# IO.net
KiCad netlist of a schematic drawn in Altium Designer
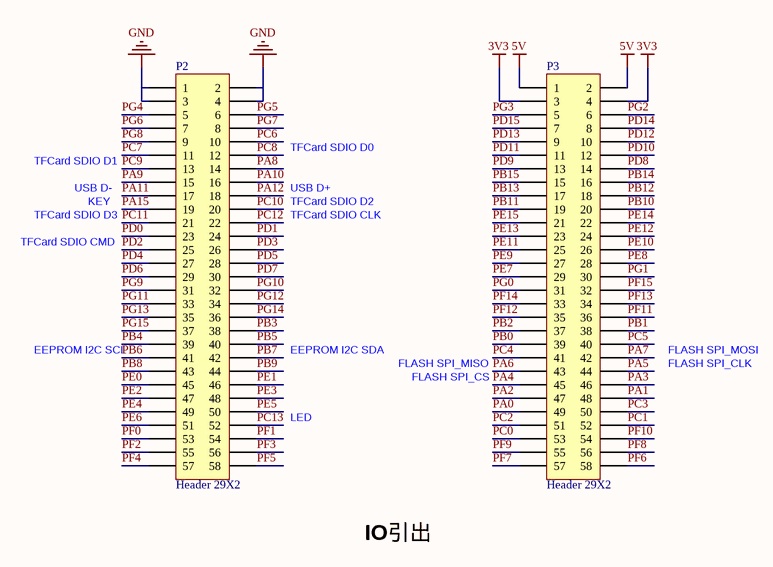
[diagram p0: 主控系统板IO引出.SchDoc]

(export (version "E")
  (design (tool "Eeschema 10.0.6"))
  (components
    (comp (ref "P2")
      (value "Header 29X2")
      (footprint "HDR2X29")
      (libsource (lib "altium-import") (part "root_0_Header 29X2_"))
    )
    (comp (ref "P3")
      (value "Header 29X2")
      (footprint "HDR2X29")
      (libsource (lib "altium-import") (part "root_0_Header 29X2_"))
    )
  )
  (nets
    (net (code "1") (name "/PA0") (class "Default")
      (node (ref "P3") (pin "49") (pinfunction "49_49") (pintype "passive"))
    )
    (net (code "2") (name "/PA1") (class "Default")
      (node (ref "P3") (pin "48") (pinfunction "48_48") (pintype "passive"))
    )
    (net (code "3") (name "/PA2") (class "Default")
      (node (ref "P3") (pin "47") (pinfunction "47_47") (pintype "passive"))
    )
    (net (code "4") (name "/PA3") (class "Default")
      (node (ref "P3") (pin "46") (pinfunction "46_46") (pintype "passive"))
    )
    (net (code "5") (name "/PA4") (class "Default")
      (node (ref "P3") (pin "45") (pinfunction "45_45") (pintype "passive"))
    )
    (net (code "6") (name "/PA5") (class "Default")
      (node (ref "P3") (pin "44") (pinfunction "44_44") (pintype "passive"))
    )
    (net (code "7") (name "/PA6") (class "Default")
      (node (ref "P3") (pin "43") (pinfunction "43_43") (pintype "passive"))
    )
    (net (code "8") (name "/PA7") (class "Default")
      (node (ref "P3") (pin "42") (pinfunction "42_42") (pintype "passive"))
    )
    (net (code "9") (name "/PA8") (class "Default")
      (node (ref "P2") (pin "14") (pinfunction "14_14") (pintype "passive"))
    )
    (net (code "10") (name "/PA9") (class "Default")
      (node (ref "P2") (pin "15") (pinfunction "15_15") (pintype "passive"))
    )
    (net (code "11") (name "/PA10") (class "Default")
      (node (ref "P2") (pin "16") (pinfunction "16_16") (pintype "passive"))
    )
    (net (code "12") (name "/PA11") (class "Default")
      (node (ref "P2") (pin "17") (pinfunction "17_17") (pintype "passive"))
    )
    (net (code "13") (name "/PA12") (class "Default")
      (node (ref "P2") (pin "18") (pinfunction "18_18") (pintype "passive"))
    )
    (net (code "14") (name "/PA15") (class "Default")
      (node (ref "P2") (pin "19") (pinfunction "19_19") (pintype "passive"))
    )
    (net (code "15") (name "/PB0") (class "Default")
      (node (ref "P3") (pin "39") (pinfunction "39_39") (pintype "passive"))
    )
    (net (code "16") (name "/PB1") (class "Default")
      (node (ref "P3") (pin "38") (pinfunction "38_38") (pintype "passive"))
    )
    (net (code "17") (name "/PB2") (class "Default")
      (node (ref "P3") (pin "37") (pinfunction "37_37") (pintype "passive"))
    )
    (net (code "18") (name "/PB3") (class "Default")
      (node (ref "P2") (pin "38") (pinfunction "38_38") (pintype "passive"))
    )
    (net (code "19") (name "/PB4") (class "Default")
      (node (ref "P2") (pin "39") (pinfunction "39_39") (pintype "passive"))
    )
    (net (code "20") (name "/PB5") (class "Default")
      (node (ref "P2") (pin "40") (pinfunction "40_40") (pintype "passive"))
    )
    (net (code "21") (name "/PB6") (class "Default")
      (node (ref "P2") (pin "41") (pinfunction "41_41") (pintype "passive"))
    )
    (net (code "22") (name "/PB7") (class "Default")
      (node (ref "P2") (pin "42") (pinfunction "42_42") (pintype "passive"))
    )
    (net (code "23") (name "/PB8") (class "Default")
      (node (ref "P2") (pin "43") (pinfunction "43_43") (pintype "passive"))
    )
    (net (code "24") (name "/PB9") (class "Default")
      (node (ref "P2") (pin "44") (pinfunction "44_44") (pintype "passive"))
    )
    (net (code "25") (name "/PB10") (class "Default")
      (node (ref "P3") (pin "20") (pinfunction "20_20") (pintype "passive"))
    )
    (net (code "26") (name "/PB11") (class "Default")
      (node (ref "P3") (pin "19") (pinfunction "19_19") (pintype "passive"))
    )
    (net (code "27") (name "/PB12") (class "Default")
      (node (ref "P3") (pin "18") (pinfunction "18_18") (pintype "passive"))
    )
    (net (code "28") (name "/PB13") (class "Default")
      (node (ref "P3") (pin "17") (pinfunction "17_17") (pintype "passive"))
    )
    (net (code "29") (name "/PB14") (class "Default")
      (node (ref "P3") (pin "16") (pinfunction "16_16") (pintype "passive"))
    )
    (net (code "30") (name "/PB15") (class "Default")
      (node (ref "P3") (pin "15") (pinfunction "15_15") (pintype "passive"))
    )
    (net (code "31") (name "/PC0") (class "Default")
      (node (ref "P3") (pin "53") (pinfunction "53_53") (pintype "passive"))
    )
    (net (code "32") (name "/PC1") (class "Default")
      (node (ref "P3") (pin "52") (pinfunction "52_52") (pintype "passive"))
    )
    (net (code "33") (name "/PC2") (class "Default")
      (node (ref "P3") (pin "51") (pinfunction "51_51") (pintype "passive"))
    )
    (net (code "34") (name "/PC3") (class "Default")
      (node (ref "P3") (pin "50") (pinfunction "50_50") (pintype "passive"))
    )
    (net (code "35") (name "/PC4") (class "Default")
      (node (ref "P3") (pin "41") (pinfunction "41_41") (pintype "passive"))
    )
    (net (code "36") (name "/PC5") (class "Default")
      (node (ref "P3") (pin "40") (pinfunction "40_40") (pintype "passive"))
    )
    (net (code "37") (name "/PC6") (class "Default")
      (node (ref "P2") (pin "10") (pinfunction "10_10") (pintype "passive"))
    )
    (net (code "38") (name "/PC7") (class "Default")
      (node (ref "P2") (pin "11") (pinfunction "11_11") (pintype "passive"))
    )
    (net (code "39") (name "/PC8") (class "Default")
      (node (ref "P2") (pin "12") (pinfunction "12_12") (pintype "passive"))
    )
    (net (code "40") (name "/PC9") (class "Default")
      (node (ref "P2") (pin "13") (pinfunction "13_13") (pintype "passive"))
    )
    (net (code "41") (name "/PC10") (class "Default")
      (node (ref "P2") (pin "20") (pinfunction "20_20") (pintype "passive"))
    )
    (net (code "42") (name "/PC11") (class "Default")
      (node (ref "P2") (pin "21") (pinfunction "21_21") (pintype "passive"))
    )
    (net (code "43") (name "/PC12") (class "Default")
      (node (ref "P2") (pin "22") (pinfunction "22_22") (pintype "passive"))
    )
    (net (code "44") (name "/PC13") (class "Default")
      (node (ref "P2") (pin "52") (pinfunction "52_52") (pintype "passive"))
    )
    (net (code "45") (name "/PD0") (class "Default")
      (node (ref "P2") (pin "23") (pinfunction "23_23") (pintype "passive"))
    )
    (net (code "46") (name "/PD1") (class "Default")
      (node (ref "P2") (pin "24") (pinfunction "24_24") (pintype "passive"))
    )
    (net (code "47") (name "/PD2") (class "Default")
      (node (ref "P2") (pin "25") (pinfunction "25_25") (pintype "passive"))
    )
    (net (code "48") (name "/PD3") (class "Default")
      (node (ref "P2") (pin "26") (pinfunction "26_26") (pintype "passive"))
    )
    (net (code "49") (name "/PD4") (class "Default")
      (node (ref "P2") (pin "27") (pinfunction "27_27") (pintype "passive"))
    )
    (net (code "50") (name "/PD5") (class "Default")
      (node (ref "P2") (pin "28") (pinfunction "28_28") (pintype "passive"))
    )
    (net (code "51") (name "/PD6") (class "Default")
      (node (ref "P2") (pin "29") (pinfunction "29_29") (pintype "passive"))
    )
    (net (code "52") (name "/PD7") (class "Default")
      (node (ref "P2") (pin "30") (pinfunction "30_30") (pintype "passive"))
    )
    (net (code "53") (name "/PD8") (class "Default")
      (node (ref "P3") (pin "14") (pinfunction "14_14") (pintype "passive"))
    )
    (net (code "54") (name "/PD9") (class "Default")
      (node (ref "P3") (pin "13") (pinfunction "13_13") (pintype "passive"))
    )
    (net (code "55") (name "/PD10") (class "Default")
      (node (ref "P3") (pin "12") (pinfunction "12_12") (pintype "passive"))
    )
    (net (code "56") (name "/PD11") (class "Default")
      (node (ref "P3") (pin "11") (pinfunction "11_11") (pintype "passive"))
    )
    (net (code "57") (name "/PD12") (class "Default")
      (node (ref "P3") (pin "10") (pinfunction "10_10") (pintype "passive"))
    )
    (net (code "58") (name "/PD13") (class "Default")
      (node (ref "P3") (pin "9") (pinfunction "9_9") (pintype "passive"))
    )
    (net (code "59") (name "/PD14") (class "Default")
      (node (ref "P3") (pin "8") (pinfunction "8_8") (pintype "passive"))
    )
    (net (code "60") (name "/PD15") (class "Default")
      (node (ref "P3") (pin "7") (pinfunction "7_7") (pintype "passive"))
    )
    (net (code "61") (name "/PE0") (class "Default")
      (node (ref "P2") (pin "45") (pinfunction "45_45") (pintype "passive"))
    )
    (net (code "62") (name "/PE1") (class "Default")
      (node (ref "P2") (pin "46") (pinfunction "46_46") (pintype "passive"))
    )
    (net (code "63") (name "/PE2") (class "Default")
      (node (ref "P2") (pin "47") (pinfunction "47_47") (pintype "passive"))
    )
    (net (code "64") (name "/PE3") (class "Default")
      (node (ref "P2") (pin "48") (pinfunction "48_48") (pintype "passive"))
    )
    (net (code "65") (name "/PE4") (class "Default")
      (node (ref "P2") (pin "49") (pinfunction "49_49") (pintype "passive"))
    )
    (net (code "66") (name "/PE5") (class "Default")
      (node (ref "P2") (pin "50") (pinfunction "50_50") (pintype "passive"))
    )
    (net (code "67") (name "/PE6") (class "Default")
      (node (ref "P2") (pin "51") (pinfunction "51_51") (pintype "passive"))
    )
    (net (code "68") (name "/PE7") (class "Default")
      (node (ref "P3") (pin "29") (pinfunction "29_29") (pintype "passive"))
    )
    (net (code "69") (name "/PE8") (class "Default")
      (node (ref "P3") (pin "28") (pinfunction "28_28") (pintype "passive"))
    )
    (net (code "70") (name "/PE9") (class "Default")
      (node (ref "P3") (pin "27") (pinfunction "27_27") (pintype "passive"))
    )
    (net (code "71") (name "/PE10") (class "Default")
      (node (ref "P3") (pin "26") (pinfunction "26_26") (pintype "passive"))
    )
    (net (code "72") (name "/PE11") (class "Default")
      (node (ref "P3") (pin "25") (pinfunction "25_25") (pintype "passive"))
    )
    (net (code "73") (name "/PE12") (class "Default")
      (node (ref "P3") (pin "24") (pinfunction "24_24") (pintype "passive"))
    )
    (net (code "74") (name "/PE13") (class "Default")
      (node (ref "P3") (pin "23") (pinfunction "23_23") (pintype "passive"))
    )
    (net (code "75") (name "/PE14") (class "Default")
      (node (ref "P3") (pin "22") (pinfunction "22_22") (pintype "passive"))
    )
    (net (code "76") (name "/PE15") (class "Default")
      (node (ref "P3") (pin "21") (pinfunction "21_21") (pintype "passive"))
    )
    (net (code "77") (name "/PF0") (class "Default")
      (node (ref "P2") (pin "53") (pinfunction "53_53") (pintype "passive"))
    )
    (net (code "78") (name "/PF1") (class "Default")
      (node (ref "P2") (pin "54") (pinfunction "54_54") (pintype "passive"))
    )
    (net (code "79") (name "/PF2") (class "Default")
      (node (ref "P2") (pin "55") (pinfunction "55_55") (pintype "passive"))
    )
    (net (code "80") (name "/PF3") (class "Default")
      (node (ref "P2") (pin "56") (pinfunction "56_56") (pintype "passive"))
    )
    (net (code "81") (name "/PF4") (class "Default")
      (node (ref "P2") (pin "57") (pinfunction "57_57") (pintype "passive"))
    )
    (net (code "82") (name "/PF5") (class "Default")
      (node (ref "P2") (pin "58") (pinfunction "58_58") (pintype "passive"))
    )
    (net (code "83") (name "/PF6") (class "Default")
      (node (ref "P3") (pin "58") (pinfunction "58_58") (pintype "passive"))
    )
    (net (code "84") (name "/PF7") (class "Default")
      (node (ref "P3") (pin "57") (pinfunction "57_57") (pintype "passive"))
    )
    (net (code "85") (name "/PF8") (class "Default")
      (node (ref "P3") (pin "56") (pinfunction "56_56") (pintype "passive"))
    )
    (net (code "86") (name "/PF9") (class "Default")
      (node (ref "P3") (pin "55") (pinfunction "55_55") (pintype "passive"))
    )
    (net (code "87") (name "/PF10") (class "Default")
      (node (ref "P3") (pin "54") (pinfunction "54_54") (pintype "passive"))
    )
    (net (code "88") (name "/PF11") (class "Default")
      (node (ref "P3") (pin "36") (pinfunction "36_36") (pintype "passive"))
    )
    (net (code "89") (name "/PF12") (class "Default")
      (node (ref "P3") (pin "35") (pinfunction "35_35") (pintype "passive"))
    )
    (net (code "90") (name "/PF13") (class "Default")
      (node (ref "P3") (pin "34") (pinfunction "34_34") (pintype "passive"))
    )
    (net (code "91") (name "/PF14") (class "Default")
      (node (ref "P3") (pin "33") (pinfunction "33_33") (pintype "passive"))
    )
    (net (code "92") (name "/PF15") (class "Default")
      (node (ref "P3") (pin "32") (pinfunction "32_32") (pintype "passive"))
    )
    (net (code "93") (name "/PG0") (class "Default")
      (node (ref "P3") (pin "31") (pinfunction "31_31") (pintype "passive"))
    )
    (net (code "94") (name "/PG1") (class "Default")
      (node (ref "P3") (pin "30") (pinfunction "30_30") (pintype "passive"))
    )
    (net (code "95") (name "/PG2") (class "Default")
      (node (ref "P3") (pin "6") (pinfunction "6_6") (pintype "passive"))
    )
    (net (code "96") (name "/PG3") (class "Default")
      (node (ref "P3") (pin "5") (pinfunction "5_5") (pintype "passive"))
    )
    (net (code "97") (name "/PG4") (class "Default")
      (node (ref "P2") (pin "5") (pinfunction "5_5") (pintype "passive"))
    )
    (net (code "98") (name "/PG5") (class "Default")
      (node (ref "P2") (pin "6") (pinfunction "6_6") (pintype "passive"))
    )
    (net (code "99") (name "/PG6") (class "Default")
      (node (ref "P2") (pin "7") (pinfunction "7_7") (pintype "passive"))
    )
    (net (code "100") (name "/PG7") (class "Default")
      (node (ref "P2") (pin "8") (pinfunction "8_8") (pintype "passive"))
    )
    (net (code "101") (name "/PG8") (class "Default")
      (node (ref "P2") (pin "9") (pinfunction "9_9") (pintype "passive"))
    )
    (net (code "102") (name "/PG9") (class "Default")
      (node (ref "P2") (pin "31") (pinfunction "31_31") (pintype "passive"))
    )
    (net (code "103") (name "/PG10") (class "Default")
      (node (ref "P2") (pin "32") (pinfunction "32_32") (pintype "passive"))
    )
    (net (code "104") (name "/PG11") (class "Default")
      (node (ref "P2") (pin "33") (pinfunction "33_33") (pintype "passive"))
    )
    (net (code "105") (name "/PG12") (class "Default")
      (node (ref "P2") (pin "34") (pinfunction "34_34") (pintype "passive"))
    )
    (net (code "106") (name "/PG13") (class "Default")
      (node (ref "P2") (pin "35") (pinfunction "35_35") (pintype "passive"))
    )
    (net (code "107") (name "/PG14") (class "Default")
      (node (ref "P2") (pin "36") (pinfunction "36_36") (pintype "passive"))
    )
    (net (code "108") (name "/PG15") (class "Default")
      (node (ref "P2") (pin "37") (pinfunction "37_37") (pintype "passive"))
    )
    (net (code "109") (name "3V3") (class "Default")
      (node (ref "P3") (pin "3") (pinfunction "3_3") (pintype "passive"))
      (node (ref "P3") (pin "4") (pinfunction "4_4") (pintype "passive"))
    )
    (net (code "110") (name "5V") (class "Default")
      (node (ref "P3") (pin "1") (pinfunction "1_1") (pintype "passive"))
      (node (ref "P3") (pin "2") (pinfunction "2_2") (pintype "passive"))
    )
    (net (code "111") (name "GND") (class "Default")
      (node (ref "P2") (pin "1") (pinfunction "1_1") (pintype "passive"))
      (node (ref "P2") (pin "2") (pinfunction "2_2") (pintype "passive"))
      (node (ref "P2") (pin "3") (pinfunction "3_3") (pintype "passive"))
      (node (ref "P2") (pin "4") (pinfunction "4_4") (pintype "passive"))
    )
  )
)
